# ursus-flow.net
KiCad netlist of a schematic drawn in EAGLE
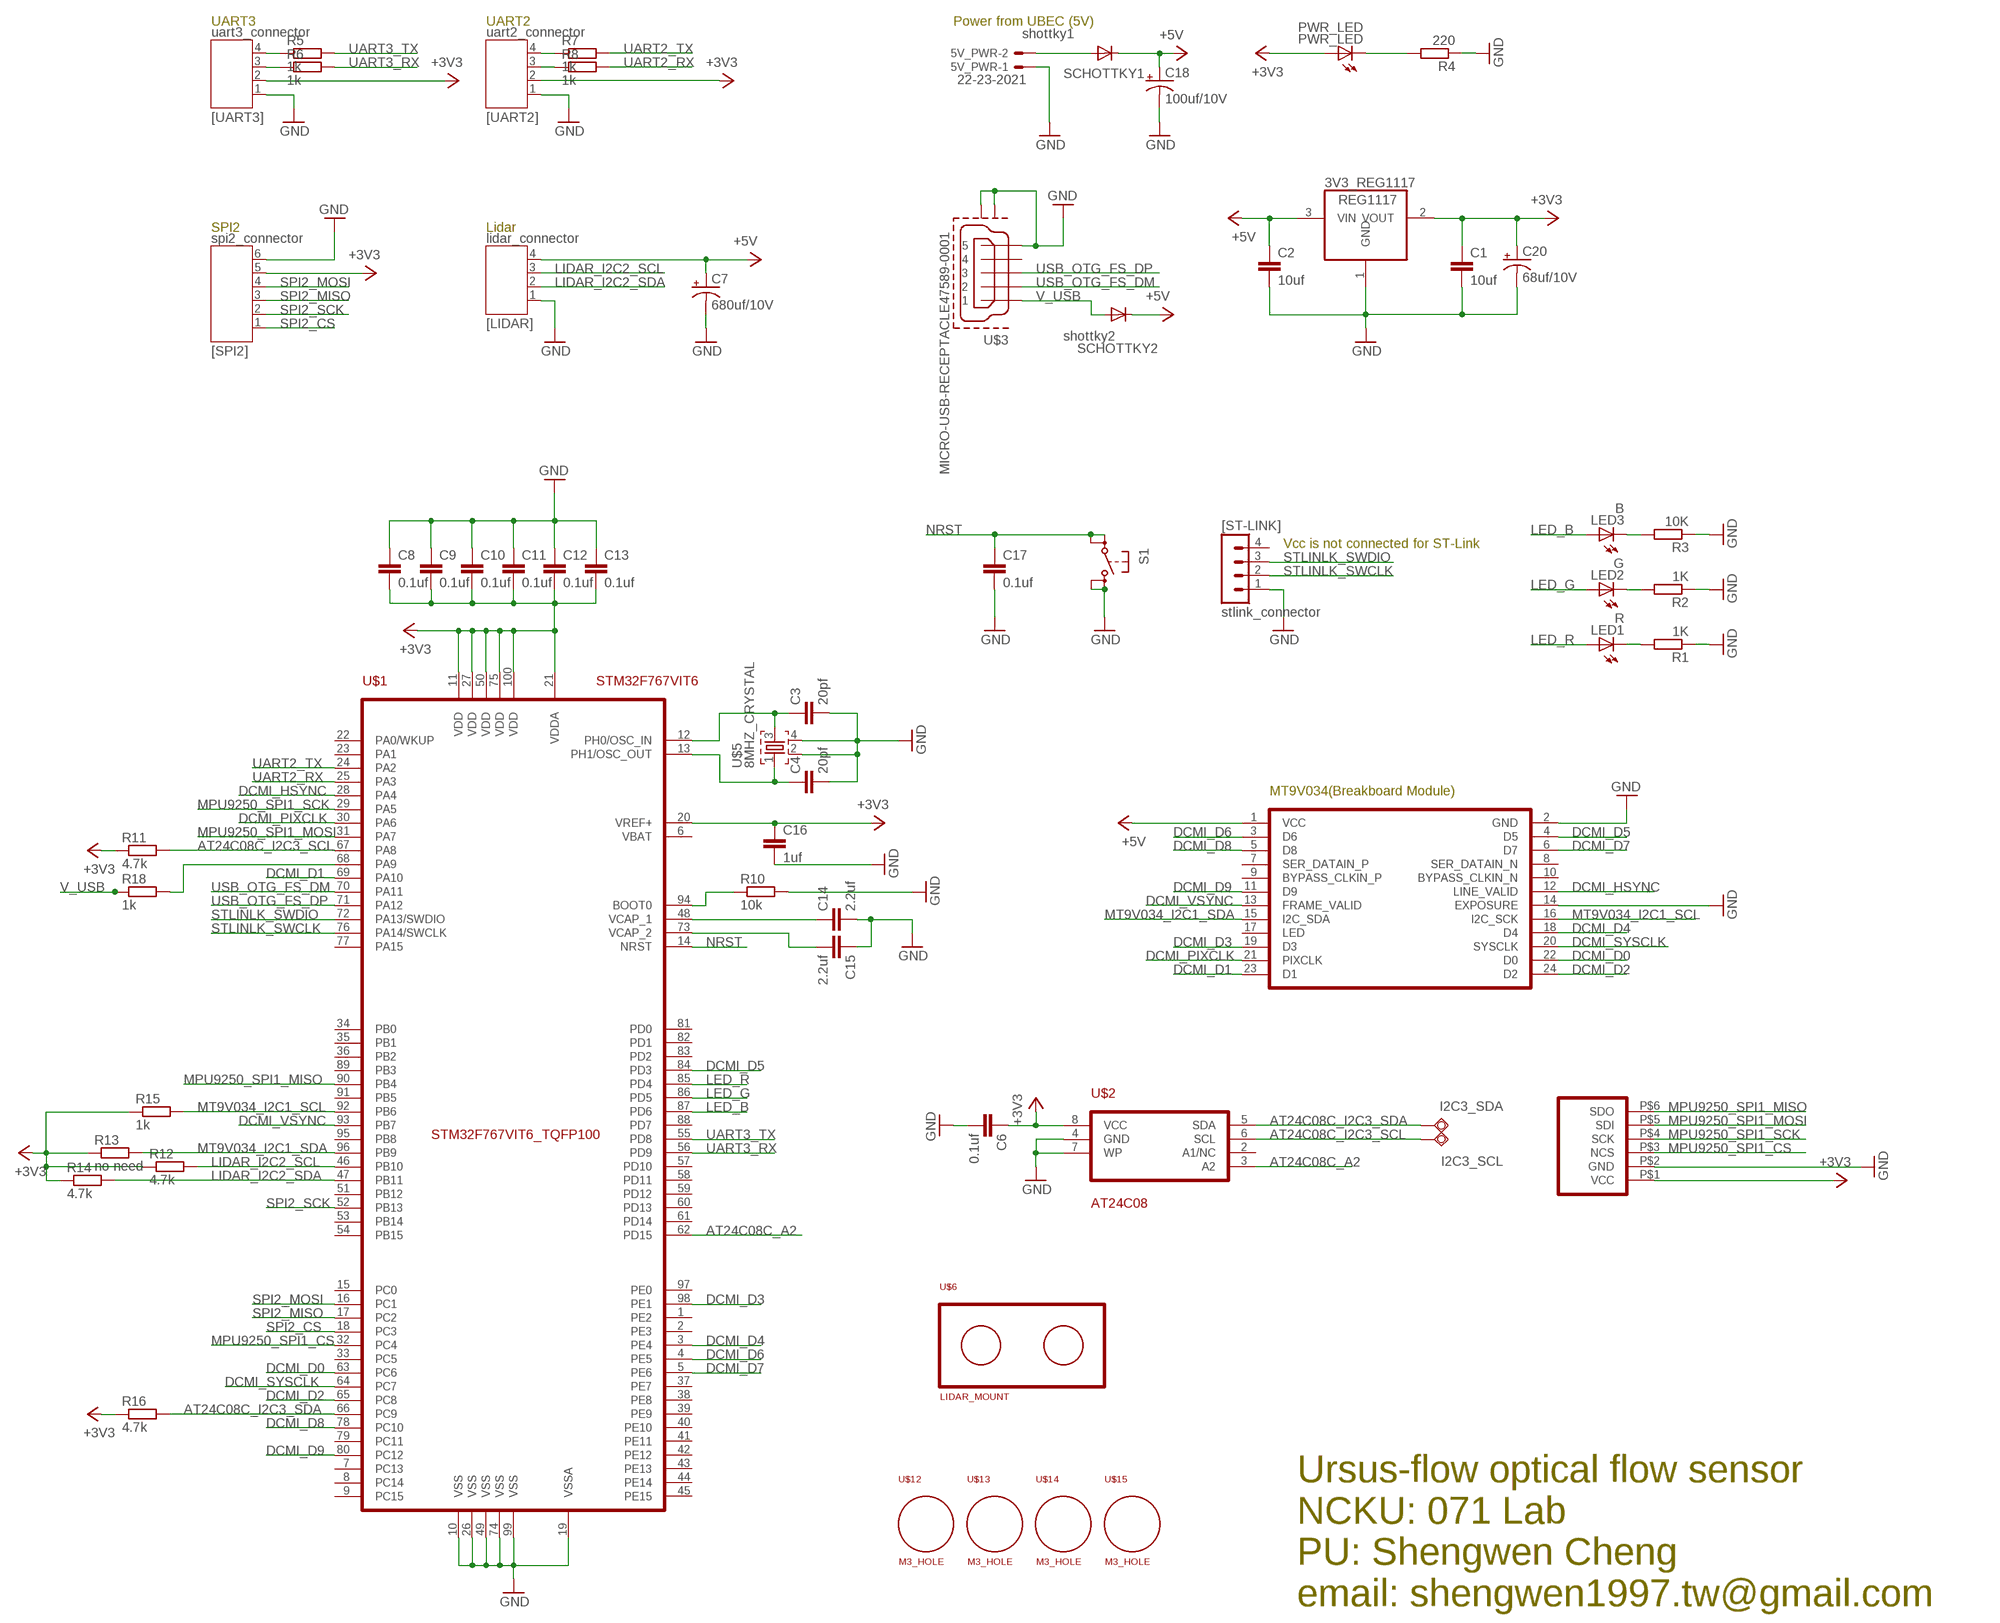
[diagram p0: schematic, sheet 1]

(export (version "E")
  (design (tool "Eeschema 10.0.6"))
  (components
    (comp (ref "3V3_REG1117")
      (value "REG1117")
      (footprint "eagle-import:SOT223")
      (libsource (lib "eagle-import") (part "REG1117"))
    )
    (comp (ref "5V_PWR")
      (value "22-23-2021")
      (footprint "eagle-import:22-23-2021")
      (fields (field (name "MF") "MOLEX"))
      (libsource (lib "eagle-import") (part "22-23-2021"))
    )
    (comp (ref "C1")
      (value "10uf")
      (footprint "eagle-import:C0805K")
      (libsource (lib "eagle-import") (part "C-EUC0805K"))
    )
    (comp (ref "C2")
      (value "10uf")
      (footprint "eagle-import:C0805K")
      (libsource (lib "eagle-import") (part "C-EUC0805K"))
    )
    (comp (ref "C3")
      (value "20pf")
      (footprint "eagle-import:C0805")
      (libsource (lib "eagle-import") (part "C-EUC0805"))
    )
    (comp (ref "C4")
      (value "20pf")
      (footprint "eagle-import:C0805")
      (libsource (lib "eagle-import") (part "C-EUC0805"))
    )
    (comp (ref "C6")
      (value "0.1uf")
      (footprint "eagle-import:C0805")
      (libsource (lib "eagle-import") (part "C-EUC0805"))
    )
    (comp (ref "C7")
      (value "680uf/10V")
      (footprint "eagle-import:D_7343-31W")
      (libsource (lib "eagle-import") (part "CPOL-USD/7343-31W"))
    )
    (comp (ref "C8")
      (value "0.1uf")
      (footprint "eagle-import:C0805")
      (libsource (lib "eagle-import") (part "C-EUC0805"))
    )
    (comp (ref "C9")
      (value "0.1uf")
      (footprint "eagle-import:C0805")
      (libsource (lib "eagle-import") (part "C-EUC0805"))
    )
    (comp (ref "C10")
      (value "0.1uf")
      (footprint "eagle-import:C0805")
      (libsource (lib "eagle-import") (part "C-EUC0805"))
    )
    (comp (ref "C11")
      (value "0.1uf")
      (footprint "eagle-import:C0805")
      (libsource (lib "eagle-import") (part "C-EUC0805"))
    )
    (comp (ref "C12")
      (value "0.1uf")
      (footprint "eagle-import:C0805")
      (libsource (lib "eagle-import") (part "C-EUC0805"))
    )
    (comp (ref "C13")
      (value "0.1uf")
      (footprint "eagle-import:C0805")
      (libsource (lib "eagle-import") (part "C-EUC0805"))
    )
    (comp (ref "C14")
      (value "2.2uf")
      (footprint "eagle-import:C0805")
      (libsource (lib "eagle-import") (part "C-EUC0805"))
    )
    (comp (ref "C15")
      (value "2.2uf")
      (footprint "eagle-import:C0805")
      (libsource (lib "eagle-import") (part "C-EUC0805"))
    )
    (comp (ref "C16")
      (value "1uf")
      (footprint "eagle-import:C0805")
      (libsource (lib "eagle-import") (part "C-EUC0805"))
    )
    (comp (ref "C17")
      (value "0.1uf")
      (footprint "eagle-import:C0805")
      (libsource (lib "eagle-import") (part "C-EUC0805"))
    )
    (comp (ref "C18")
      (value "100uf/10V")
      (footprint "eagle-import:C_6032-28R")
      (libsource (lib "eagle-import") (part "CPOL-USC/6032-28R"))
    )
    (comp (ref "C20")
      (value "68uf/10V")
      (footprint "eagle-import:B_3528-21W")
      (libsource (lib "eagle-import") (part "CPOL-USB/3528-21W"))
    )
    (comp (ref "I2C3_SCL")
      (value "TPSQTP20SQ")
      (footprint "eagle-import:TP20SQ")
      (libsource (lib "eagle-import") (part "TPSQTP20SQ"))
    )
    (comp (ref "I2C3_SDA")
      (value "TPSQTP20SQ")
      (footprint "eagle-import:TP20SQ")
      (libsource (lib "eagle-import") (part "TPSQTP20SQ"))
    )
    (comp (ref "LED1")
      (value "R")
      (footprint "eagle-import:SML0805")
      (libsource (lib "eagle-import") (part "LEDSML0805"))
    )
    (comp (ref "LED2")
      (value "G")
      (footprint "eagle-import:SML0805")
      (libsource (lib "eagle-import") (part "LEDSML0805"))
    )
    (comp (ref "LED3")
      (value "B")
      (footprint "eagle-import:SML0805")
      (libsource (lib "eagle-import") (part "LEDSML0805"))
    )
    (comp (ref "PWR_LED")
      (value "PWR_LED")
      (footprint "eagle-import:SML0805")
      (libsource (lib "eagle-import") (part "LEDSML0805"))
    )
    (comp (ref "R1")
      (value "1K")
      (footprint "eagle-import:R0805W")
      (libsource (lib "eagle-import") (part "resistor_R-EU_R0805W"))
    )
    (comp (ref "R2")
      (value "1K")
      (footprint "eagle-import:R0805W")
      (libsource (lib "eagle-import") (part "resistor_R-EU_R0805W"))
    )
    (comp (ref "R3")
      (value "10K")
      (footprint "eagle-import:R0805W")
      (libsource (lib "eagle-import") (part "resistor_R-EU_R0805W"))
    )
    (comp (ref "R4")
      (value "220")
      (footprint "eagle-import:R0805W")
      (libsource (lib "eagle-import") (part "resistor_R-EU_R0805W"))
    )
    (comp (ref "R5")
      (value "1k")
      (footprint "eagle-import:M0805")
      (libsource (lib "eagle-import") (part "R-EU_M0805"))
    )
    (comp (ref "R6")
      (value "1k")
      (footprint "eagle-import:M0805")
      (libsource (lib "eagle-import") (part "R-EU_M0805"))
    )
    (comp (ref "R7")
      (value "1k")
      (footprint "eagle-import:M0805")
      (libsource (lib "eagle-import") (part "R-EU_M0805"))
    )
    (comp (ref "R8")
      (value "1k")
      (footprint "eagle-import:M0805")
      (libsource (lib "eagle-import") (part "R-EU_M0805"))
    )
    (comp (ref "R10")
      (value "10k")
      (footprint "eagle-import:R0805W")
      (libsource (lib "eagle-import") (part "resistor_R-EU_R0805W"))
    )
    (comp (ref "R11")
      (value "4.7k")
      (footprint "eagle-import:R0805W")
      (libsource (lib "eagle-import") (part "resistor_R-EU_R0805W"))
    )
    (comp (ref "R12")
      (value "4.7k")
      (footprint "eagle-import:R0805W")
      (libsource (lib "eagle-import") (part "resistor_R-EU_R0805W"))
    )
    (comp (ref "R13")
      (value "no need")
      (footprint "eagle-import:R0805W")
      (libsource (lib "eagle-import") (part "resistor_R-EU_R0805W"))
    )
    (comp (ref "R14")
      (value "4.7k")
      (footprint "eagle-import:R0805W")
      (libsource (lib "eagle-import") (part "resistor_R-EU_R0805W"))
    )
    (comp (ref "R15")
      (value "1k")
      (footprint "eagle-import:R0805W")
      (libsource (lib "eagle-import") (part "resistor_R-EU_R0805W"))
    )
    (comp (ref "R16")
      (value "4.7k")
      (footprint "eagle-import:R0805W")
      (libsource (lib "eagle-import") (part "resistor_R-EU_R0805W"))
    )
    (comp (ref "R18")
      (value "1k")
      (footprint "eagle-import:R0805W")
      (libsource (lib "eagle-import") (part "resistor_R-EU_R0805W"))
    )
    (comp (ref "S1")
      (value "EVQPSL/Q")
      (footprint "eagle-import:EVQPSL_Q")
      (libsource (lib "eagle-import") (part "EVQPSL/Q"))
    )
    (comp (ref "SCHOTTKY1")
      (value "shottky1")
      (footprint "eagle-import:SOD323-W")
      (libsource (lib "eagle-import") (part "DIODE-SOD323-W"))
    )
    (comp (ref "SCHOTTKY2")
      (value "shottky2")
      (footprint "eagle-import:SOD323-W")
      (libsource (lib "eagle-import") (part "DIODE-SOD323-W"))
    )
    (comp (ref "U$1")
      (value "STM32F767VIT6")
      (footprint "eagle-import:STM32F767VIT6")
      (libsource (lib "eagle-import") (part "STM32F767VIT6"))
    )
    (comp (ref "U$2")
      (value "AT24C08")
      (footprint "eagle-import:SO8")
      (libsource (lib "eagle-import") (part "AT24C08"))
    )
    (comp (ref "U$3")
      (value "MICRO-USB-RECEPTACLE47589-0001")
      (footprint "eagle-import:47589-0001")
      (libsource (lib "eagle-import") (part "MICRO-USB-RECEPTACLE47589-0001"))
    )
    (comp (ref "U$4")
      (value "MT9V034_MODULE")
      (footprint "eagle-import:MA12-2")
      (libsource (lib "eagle-import") (part "MT9V034_MODULE"))
    )
    (comp (ref "U$5")
      (value "8MHZ_CRYSTAL")
      (footprint "eagle-import:8MHZ_CRYSTAL")
      (libsource (lib "eagle-import") (part "8MHZ_CRYSTAL"))
    )
    (comp (ref "U$6")
      (value "LIDAR_MOUNT")
      (footprint "eagle-import:LIDAR_MOUNT")
      (libsource (lib "eagle-import") (part "LIDAR_MOUNT"))
    )
    (comp (ref "U$11")
      (value "MPU9250_BREAKOUT")
      (footprint "eagle-import:MPU9250_BREAKOUT")
      (libsource (lib "eagle-import") (part "MPU9250_BREAKOUT"))
    )
    (comp (ref "U$12")
      (value "M3_HOLE")
      (footprint "eagle-import:M3_HOLE")
      (libsource (lib "eagle-import") (part "M3_HOLE"))
    )
    (comp (ref "U$13")
      (value "M3_HOLE")
      (footprint "eagle-import:M3_HOLE")
      (libsource (lib "eagle-import") (part "M3_HOLE"))
    )
    (comp (ref "U$14")
      (value "M3_HOLE")
      (footprint "eagle-import:M3_HOLE")
      (libsource (lib "eagle-import") (part "M3_HOLE"))
    )
    (comp (ref "U$15")
      (value "M3_HOLE")
      (footprint "eagle-import:M3_HOLE")
      (libsource (lib "eagle-import") (part "M3_HOLE"))
    )
    (comp (ref "[LIDAR]")
      (value "lidar_connector")
      (footprint "eagle-import:JST-PH4")
      (libsource (lib "eagle-import") (part "JST-PH4"))
    )
    (comp (ref "[SPI2]")
      (value "spi2_connector")
      (footprint "eagle-import:JST-PH6")
      (libsource (lib "eagle-import") (part "JST-PH6"))
    )
    (comp (ref "[ST-LINK]")
      (value "stlink_connector")
      (footprint "eagle-import:MA04-1")
      (libsource (lib "eagle-import") (part "MA04-1"))
    )
    (comp (ref "[UART2]")
      (value "uart2_connector")
      (footprint "eagle-import:JST-PH4")
      (libsource (lib "eagle-import") (part "JST-PH4"))
    )
    (comp (ref "[UART3]")
      (value "uart3_connector")
      (footprint "eagle-import:JST-PH4")
      (libsource (lib "eagle-import") (part "JST-PH4"))
    )
  )
  (nets
    (net (code "1") (name "+3V3") (class "Default")
      (node (ref "3V3_REG1117") (pin "2") (pinfunction "VOUT_2") (pintype "output"))
      (node (ref "C1") (pin "1") (pinfunction "1_1") (pintype "passive"))
      (node (ref "C10") (pin "2") (pinfunction "2_2") (pintype "passive"))
      (node (ref "C11") (pin "2") (pinfunction "2_2") (pintype "passive"))
      (node (ref "C12") (pin "2") (pinfunction "2_2") (pintype "passive"))
      (node (ref "C13") (pin "2") (pinfunction "2_2") (pintype "passive"))
      (node (ref "C16") (pin "1") (pinfunction "1_1") (pintype "passive"))
      (node (ref "C20") (pin "+") (pinfunction "+_+") (pintype "passive"))
      (node (ref "C6") (pin "1") (pinfunction "1_1") (pintype "passive"))
      (node (ref "C8") (pin "2") (pinfunction "2_2") (pintype "passive"))
      (node (ref "C9") (pin "2") (pinfunction "2_2") (pintype "passive"))
      (node (ref "PWR_LED") (pin "A") (pinfunction "A_A") (pintype "passive"))
      (node (ref "R11") (pin "1") (pinfunction "1_1") (pintype "passive"))
      (node (ref "R12") (pin "1") (pinfunction "1_1") (pintype "passive"))
      (node (ref "R13") (pin "1") (pinfunction "1_1") (pintype "passive"))
      (node (ref "R14") (pin "1") (pinfunction "1_1") (pintype "passive"))
      (node (ref "R15") (pin "1") (pinfunction "1_1") (pintype "passive"))
      (node (ref "R16") (pin "1") (pinfunction "1_1") (pintype "passive"))
      (node (ref "U$1") (pin "100") (pinfunction "VDD_100") (pintype "bidirectional"))
      (node (ref "U$1") (pin "11") (pinfunction "VDD_11") (pintype "bidirectional"))
      (node (ref "U$1") (pin "20") (pinfunction "VREF+_20") (pintype "bidirectional"))
      (node (ref "U$1") (pin "21") (pinfunction "VDDA_21") (pintype "bidirectional"))
      (node (ref "U$1") (pin "27") (pinfunction "VDD_27") (pintype "bidirectional"))
      (node (ref "U$1") (pin "50") (pinfunction "VDD_50") (pintype "bidirectional"))
      (node (ref "U$1") (pin "75") (pinfunction "VDD_75") (pintype "bidirectional"))
      (node (ref "U$11") (pin "P$1") (pinfunction "VCC_P$1") (pintype "bidirectional"))
      (node (ref "U$2") (pin "8") (pinfunction "VCC_8") (pintype "bidirectional"))
      (node (ref "[SPI2]") (pin "5") (pinfunction "5_5") (pintype "passive"))
      (node (ref "[UART2]") (pin "2") (pinfunction "2_2") (pintype "passive"))
      (node (ref "[UART3]") (pin "2") (pinfunction "2_2") (pintype "passive"))
    )
    (net (code "2") (name "+5V") (class "Default")
      (node (ref "3V3_REG1117") (pin "3") (pinfunction "VIN_3") (pintype "input"))
      (node (ref "C18") (pin "+") (pinfunction "+_+") (pintype "passive"))
      (node (ref "C2") (pin "1") (pinfunction "1_1") (pintype "passive"))
      (node (ref "C7") (pin "+") (pinfunction "+_+") (pintype "passive"))
      (node (ref "SCHOTTKY1") (pin "C") (pinfunction "C_C") (pintype "passive"))
      (node (ref "SCHOTTKY2") (pin "C") (pinfunction "C_C") (pintype "passive"))
      (node (ref "U$4") (pin "1") (pinfunction "VCC_1") (pintype "bidirectional"))
      (node (ref "[LIDAR]") (pin "4") (pinfunction "4_4") (pintype "passive"))
    )
    (net (code "3") (name "/AT24C08C_A2") (class "Default")
      (node (ref "U$1") (pin "62") (pinfunction "PD15_62") (pintype "bidirectional"))
      (node (ref "U$2") (pin "3") (pinfunction "A2_3") (pintype "bidirectional"))
    )
    (net (code "4") (name "/AT24C08C_I2C3_SCL") (class "Default")
      (node (ref "I2C3_SCL") (pin "TP") (pinfunction "TP_TP") (pintype "input"))
      (node (ref "R11") (pin "2") (pinfunction "2_2") (pintype "passive"))
      (node (ref "U$1") (pin "67") (pinfunction "PA8_67") (pintype "bidirectional"))
      (node (ref "U$2") (pin "6") (pinfunction "SCL_6") (pintype "bidirectional"))
    )
    (net (code "5") (name "/AT24C08C_I2C3_SDA") (class "Default")
      (node (ref "I2C3_SDA") (pin "TP") (pinfunction "TP_TP") (pintype "input"))
      (node (ref "R16") (pin "2") (pinfunction "2_2") (pintype "passive"))
      (node (ref "U$1") (pin "66") (pinfunction "PC9_66") (pintype "bidirectional"))
      (node (ref "U$2") (pin "5") (pinfunction "SDA_5") (pintype "bidirectional"))
    )
    (net (code "6") (name "/DCMI_D0") (class "Default")
      (node (ref "U$1") (pin "63") (pinfunction "PC6_63") (pintype "bidirectional"))
      (node (ref "U$4") (pin "22") (pinfunction "D0_22") (pintype "bidirectional"))
    )
    (net (code "7") (name "/DCMI_D1") (class "Default")
      (node (ref "U$1") (pin "69") (pinfunction "PA10_69") (pintype "bidirectional"))
      (node (ref "U$4") (pin "23") (pinfunction "D1_23") (pintype "bidirectional"))
    )
    (net (code "8") (name "/DCMI_D2") (class "Default")
      (node (ref "U$1") (pin "65") (pinfunction "PC8_65") (pintype "bidirectional"))
      (node (ref "U$4") (pin "24") (pinfunction "D2_24") (pintype "bidirectional"))
    )
    (net (code "9") (name "/DCMI_D3") (class "Default")
      (node (ref "U$1") (pin "98") (pinfunction "PE1_98") (pintype "bidirectional"))
      (node (ref "U$4") (pin "19") (pinfunction "D3_19") (pintype "bidirectional"))
    )
    (net (code "10") (name "/DCMI_D4") (class "Default")
      (node (ref "U$1") (pin "3") (pinfunction "PE4_3") (pintype "bidirectional"))
      (node (ref "U$4") (pin "18") (pinfunction "D4_18") (pintype "bidirectional"))
    )
    (net (code "11") (name "/DCMI_D5") (class "Default")
      (node (ref "U$1") (pin "84") (pinfunction "PD3_84") (pintype "bidirectional"))
      (node (ref "U$4") (pin "4") (pinfunction "D5_4") (pintype "bidirectional"))
    )
    (net (code "12") (name "/DCMI_D6") (class "Default")
      (node (ref "U$1") (pin "4") (pinfunction "PE5_4") (pintype "bidirectional"))
      (node (ref "U$4") (pin "3") (pinfunction "D6_3") (pintype "bidirectional"))
    )
    (net (code "13") (name "/DCMI_D7") (class "Default")
      (node (ref "U$1") (pin "5") (pinfunction "PE6_5") (pintype "bidirectional"))
      (node (ref "U$4") (pin "6") (pinfunction "D7_6") (pintype "bidirectional"))
    )
    (net (code "14") (name "/DCMI_D8") (class "Default")
      (node (ref "U$1") (pin "78") (pinfunction "PC10_78") (pintype "bidirectional"))
      (node (ref "U$4") (pin "5") (pinfunction "D8_5") (pintype "bidirectional"))
    )
    (net (code "15") (name "/DCMI_D9") (class "Default")
      (node (ref "U$1") (pin "80") (pinfunction "PC12_80") (pintype "bidirectional"))
      (node (ref "U$4") (pin "11") (pinfunction "D9_11") (pintype "bidirectional"))
    )
    (net (code "16") (name "/DCMI_HSYNC") (class "Default")
      (node (ref "U$1") (pin "28") (pinfunction "PA4_28") (pintype "bidirectional"))
      (node (ref "U$4") (pin "12") (pinfunction "LINE_VALID_12") (pintype "bidirectional"))
    )
    (net (code "17") (name "/DCMI_PIXCLK") (class "Default")
      (node (ref "U$1") (pin "30") (pinfunction "PA6_30") (pintype "bidirectional"))
      (node (ref "U$4") (pin "21") (pinfunction "PIXCLK_21") (pintype "bidirectional"))
    )
    (net (code "18") (name "/DCMI_SYSCLK") (class "Default")
      (node (ref "U$1") (pin "64") (pinfunction "PC7_64") (pintype "bidirectional"))
      (node (ref "U$4") (pin "20") (pinfunction "SYSCLK_20") (pintype "bidirectional"))
    )
    (net (code "19") (name "/DCMI_VSYNC") (class "Default")
      (node (ref "U$1") (pin "93") (pinfunction "PB7_93") (pintype "bidirectional"))
      (node (ref "U$4") (pin "13") (pinfunction "FRAME_VALID_13") (pintype "bidirectional"))
    )
    (net (code "20") (name "/LED_B") (class "Default")
      (node (ref "LED3") (pin "A") (pinfunction "A_A") (pintype "passive"))
      (node (ref "U$1") (pin "87") (pinfunction "PD6_87") (pintype "bidirectional"))
    )
    (net (code "21") (name "/LED_G") (class "Default")
      (node (ref "LED2") (pin "A") (pinfunction "A_A") (pintype "passive"))
      (node (ref "U$1") (pin "86") (pinfunction "PD5_86") (pintype "bidirectional"))
    )
    (net (code "22") (name "/LED_R") (class "Default")
      (node (ref "LED1") (pin "A") (pinfunction "A_A") (pintype "passive"))
      (node (ref "U$1") (pin "85") (pinfunction "PD4_85") (pintype "bidirectional"))
    )
    (net (code "23") (name "/LIDAR_I2C2_SCL") (class "Default")
      (node (ref "R12") (pin "2") (pinfunction "2_2") (pintype "passive"))
      (node (ref "U$1") (pin "46") (pinfunction "PB10_46") (pintype "bidirectional"))
      (node (ref "[LIDAR]") (pin "3") (pinfunction "3_3") (pintype "passive"))
    )
    (net (code "24") (name "/LIDAR_I2C2_SDA") (class "Default")
      (node (ref "R14") (pin "2") (pinfunction "2_2") (pintype "passive"))
      (node (ref "U$1") (pin "47") (pinfunction "PB11_47") (pintype "bidirectional"))
      (node (ref "[LIDAR]") (pin "2") (pinfunction "2_2") (pintype "passive"))
    )
    (net (code "25") (name "/MPU9250_SPI1_CS") (class "Default")
      (node (ref "U$1") (pin "32") (pinfunction "PC4_32") (pintype "bidirectional"))
      (node (ref "U$11") (pin "P$3") (pinfunction "NCS_P$3") (pintype "bidirectional"))
    )
    (net (code "26") (name "/MPU9250_SPI1_MISO") (class "Default")
      (node (ref "U$1") (pin "90") (pinfunction "PB4_90") (pintype "bidirectional"))
      (node (ref "U$11") (pin "P$6") (pinfunction "SDO_P$6") (pintype "bidirectional"))
    )
    (net (code "27") (name "/MPU9250_SPI1_MOSI") (class "Default")
      (node (ref "U$1") (pin "31") (pinfunction "PA7_31") (pintype "bidirectional"))
      (node (ref "U$11") (pin "P$5") (pinfunction "SDI_P$5") (pintype "bidirectional"))
    )
    (net (code "28") (name "/MPU9250_SPI1_SCK") (class "Default")
      (node (ref "U$1") (pin "29") (pinfunction "PA5_29") (pintype "bidirectional"))
      (node (ref "U$11") (pin "P$4") (pinfunction "SCK_P$4") (pintype "bidirectional"))
    )
    (net (code "29") (name "/MT9V034_I2C1_SCL") (class "Default")
      (node (ref "R15") (pin "2") (pinfunction "2_2") (pintype "passive"))
      (node (ref "U$1") (pin "92") (pinfunction "PB6_92") (pintype "bidirectional"))
      (node (ref "U$4") (pin "16") (pinfunction "I2C_SCK_16") (pintype "bidirectional"))
    )
    (net (code "30") (name "/MT9V034_I2C1_SDA") (class "Default")
      (node (ref "R13") (pin "2") (pinfunction "2_2") (pintype "passive"))
      (node (ref "U$1") (pin "96") (pinfunction "PB9_96") (pintype "bidirectional"))
      (node (ref "U$4") (pin "15") (pinfunction "I2C_SDA_15") (pintype "bidirectional"))
    )
    (net (code "31") (name "/NRST") (class "Default")
      (node (ref "C17") (pin "1") (pinfunction "1_1") (pintype "passive"))
      (node (ref "S1") (pin "A") (pinfunction "P_A") (pintype "passive"))
      (node (ref "S1") (pin "A1") (pinfunction "P1_A1") (pintype "passive"))
      (node (ref "U$1") (pin "14") (pinfunction "NRST_14") (pintype "bidirectional"))
    )
    (net (code "32") (name "/SPI2_CS") (class "Default")
      (node (ref "U$1") (pin "18") (pinfunction "PC3_18") (pintype "bidirectional"))
      (node (ref "[SPI2]") (pin "1") (pinfunction "1_1") (pintype "passive"))
    )
    (net (code "33") (name "/SPI2_MISO") (class "Default")
      (node (ref "U$1") (pin "17") (pinfunction "PC2_17") (pintype "bidirectional"))
      (node (ref "[SPI2]") (pin "3") (pinfunction "3_3") (pintype "passive"))
    )
    (net (code "34") (name "/SPI2_MOSI") (class "Default")
      (node (ref "U$1") (pin "16") (pinfunction "PC1_16") (pintype "bidirectional"))
      (node (ref "[SPI2]") (pin "4") (pinfunction "4_4") (pintype "passive"))
    )
    (net (code "35") (name "/SPI2_SCK") (class "Default")
      (node (ref "U$1") (pin "52") (pinfunction "PB13_52") (pintype "bidirectional"))
      (node (ref "[SPI2]") (pin "2") (pinfunction "2_2") (pintype "passive"))
    )
    (net (code "36") (name "/STLINLK_SWCLK") (class "Default")
      (node (ref "U$1") (pin "76") (pinfunction "PA14/SWCLK_76") (pintype "bidirectional"))
      (node (ref "[ST-LINK]") (pin "2") (pinfunction "2_2") (pintype "passive"))
    )
    (net (code "37") (name "/STLINLK_SWDIO") (class "Default")
      (node (ref "U$1") (pin "72") (pinfunction "PA13/SWDIO_72") (pintype "bidirectional"))
      (node (ref "[ST-LINK]") (pin "3") (pinfunction "3_3") (pintype "passive"))
    )
    (net (code "38") (name "/UART2_RX") (class "Default")
      (node (ref "R8") (pin "2") (pinfunction "2_2") (pintype "passive"))
      (node (ref "U$1") (pin "25") (pinfunction "PA3_25") (pintype "bidirectional"))
    )
    (net (code "39") (name "/UART2_TX") (class "Default")
      (node (ref "R7") (pin "2") (pinfunction "2_2") (pintype "passive"))
      (node (ref "U$1") (pin "24") (pinfunction "PA2_24") (pintype "bidirectional"))
    )
    (net (code "40") (name "/UART3_RX") (class "Default")
      (node (ref "R6") (pin "2") (pinfunction "2_2") (pintype "passive"))
      (node (ref "U$1") (pin "56") (pinfunction "PD9_56") (pintype "bidirectional"))
    )
    (net (code "41") (name "/UART3_TX") (class "Default")
      (node (ref "R5") (pin "2") (pinfunction "2_2") (pintype "passive"))
      (node (ref "U$1") (pin "55") (pinfunction "PD8_55") (pintype "bidirectional"))
    )
    (net (code "42") (name "/USB_OTG_FS_DM") (class "Default")
      (node (ref "U$1") (pin "70") (pinfunction "PA11_70") (pintype "bidirectional"))
      (node (ref "U$3") (pin "2") (pinfunction "2_2") (pintype "input"))
    )
    (net (code "43") (name "/USB_OTG_FS_DP") (class "Default")
      (node (ref "U$1") (pin "71") (pinfunction "PA12_71") (pintype "bidirectional"))
      (node (ref "U$3") (pin "3") (pinfunction "3_3") (pintype "input"))
    )
    (net (code "44") (name "/V_USB") (class "Default")
      (node (ref "R18") (pin "1") (pinfunction "1_1") (pintype "passive"))
      (node (ref "SCHOTTKY2") (pin "A") (pinfunction "A_A") (pintype "passive"))
      (node (ref "U$3") (pin "1") (pinfunction "1_1") (pintype "input"))
    )
    (net (code "45") (name "GND") (class "Default")
      (node (ref "3V3_REG1117") (pin "1") (pinfunction "GND_1") (pintype "power_in"))
      (node (ref "5V_PWR") (pin "1") (pinfunction "S_1") (pintype "passive"))
      (node (ref "C1") (pin "2") (pinfunction "2_2") (pintype "passive"))
      (node (ref "C10") (pin "1") (pinfunction "1_1") (pintype "passive"))
      (node (ref "C11") (pin "1") (pinfunction "1_1") (pintype "passive"))
      (node (ref "C12") (pin "1") (pinfunction "1_1") (pintype "passive"))
      (node (ref "C13") (pin "1") (pinfunction "1_1") (pintype "passive"))
      (node (ref "C14") (pin "2") (pinfunction "2_2") (pintype "passive"))
      (node (ref "C15") (pin "1") (pinfunction "1_1") (pintype "passive"))
      (node (ref "C16") (pin "2") (pinfunction "2_2") (pintype "passive"))
      (node (ref "C17") (pin "2") (pinfunction "2_2") (pintype "passive"))
      (node (ref "C18") (pin "-") (pinfunction "-_-") (pintype "passive"))
      (node (ref "C2") (pin "2") (pinfunction "2_2") (pintype "passive"))
      (node (ref "C20") (pin "-") (pinfunction "-_-") (pintype "passive"))
      (node (ref "C3") (pin "2") (pinfunction "2_2") (pintype "passive"))
      (node (ref "C4") (pin "2") (pinfunction "2_2") (pintype "passive"))
      (node (ref "C6") (pin "2") (pinfunction "2_2") (pintype "passive"))
      (node (ref "C7") (pin "-") (pinfunction "-_-") (pintype "passive"))
      (node (ref "C8") (pin "1") (pinfunction "1_1") (pintype "passive"))
      (node (ref "C9") (pin "1") (pinfunction "1_1") (pintype "passive"))
      (node (ref "R1") (pin "1") (pinfunction "1_1") (pintype "passive"))
      (node (ref "R10") (pin "2") (pinfunction "2_2") (pintype "passive"))
      (node (ref "R2") (pin "1") (pinfunction "1_1") (pintype "passive"))
      (node (ref "R3") (pin "1") (pinfunction "1_1") (pintype "passive"))
      (node (ref "R4") (pin "1") (pinfunction "1_1") (pintype "passive"))
      (node (ref "S1") (pin "B") (pinfunction "S_B") (pintype "passive"))
      (node (ref "S1") (pin "B1") (pinfunction "S1_B1") (pintype "passive"))
      (node (ref "U$1") (pin "10") (pinfunction "VSS_10") (pintype "bidirectional"))
      (node (ref "U$1") (pin "19") (pinfunction "VSSA_19") (pintype "bidirectional"))
      (node (ref "U$1") (pin "26") (pinfunction "VSS_26") (pintype "bidirectional"))
      (node (ref "U$1") (pin "49") (pinfunction "VSS_49") (pintype "bidirectional"))
      (node (ref "U$1") (pin "74") (pinfunction "VSS_74") (pintype "bidirectional"))
      (node (ref "U$1") (pin "99") (pinfunction "VSS_99") (pintype "bidirectional"))
      (node (ref "U$11") (pin "P$2") (pinfunction "GND_P$2") (pintype "bidirectional"))
      (node (ref "U$2") (pin "4") (pinfunction "GND_4") (pintype "bidirectional"))
      (node (ref "U$2") (pin "7") (pinfunction "WP_7") (pintype "bidirectional"))
      (node (ref "U$3") (pin "5") (pinfunction "5_5") (pintype "input"))
      (node (ref "U$3") (pin "CASING1") (pinfunction "GND1_CASING1") (pintype "bidirectional"))
      (node (ref "U$3") (pin "CASING2") (pinfunction "GND2_CASING2") (pintype "bidirectional"))
      (node (ref "U$4") (pin "14") (pinfunction "EXPOSURE_14") (pintype "bidirectional"))
      (node (ref "U$4") (pin "2") (pinfunction "GND_2") (pintype "bidirectional"))
      (node (ref "U$5") (pin "2") (pinfunction "2_2") (pintype "passive"))
      (node (ref "U$5") (pin "4") (pinfunction "4_4") (pintype "passive"))
      (node (ref "[LIDAR]") (pin "1") (pinfunction "1_1") (pintype "passive"))
      (node (ref "[SPI2]") (pin "6") (pinfunction "6_6") (pintype "passive"))
      (node (ref "[ST-LINK]") (pin "1") (pinfunction "1_1") (pintype "passive"))
      (node (ref "[UART2]") (pin "1") (pinfunction "1_1") (pintype "passive"))
      (node (ref "[UART3]") (pin "1") (pinfunction "1_1") (pintype "passive"))
    )
    (net (code "46") (name "Net-(5V_PWRB-S)") (class "Default")
      (node (ref "5V_PWR") (pin "2") (pinfunction "S_2") (pintype "passive"))
      (node (ref "SCHOTTKY1") (pin "A") (pinfunction "A_A") (pintype "passive"))
    )
    (net (code "47") (name "Net-(LED1-PadC)") (class "Default")
      (node (ref "LED1") (pin "C") (pinfunction "C_C") (pintype "passive"))
      (node (ref "R1") (pin "2") (pinfunction "2_2") (pintype "passive"))
    )
    (net (code "48") (name "Net-(LED2-PadC)") (class "Default")
      (node (ref "LED2") (pin "C") (pinfunction "C_C") (pintype "passive"))
      (node (ref "R2") (pin "2") (pinfunction "2_2") (pintype "passive"))
    )
    (net (code "49") (name "Net-(LED3-PadC)") (class "Default")
      (node (ref "LED3") (pin "C") (pinfunction "C_C") (pintype "passive"))
      (node (ref "R3") (pin "2") (pinfunction "2_2") (pintype "passive"))
    )
    (net (code "50") (name "Net-(PWR_LED-PadC)") (class "Default")
      (node (ref "PWR_LED") (pin "C") (pinfunction "C_C") (pintype "passive"))
      (node (ref "R4") (pin "2") (pinfunction "2_2") (pintype "passive"))
    )
    (net (code "51") (name "Net-(R5-Pad1)") (class "Default")
      (node (ref "R5") (pin "1") (pinfunction "1_1") (pintype "passive"))
      (node (ref "[UART3]") (pin "4") (pinfunction "4_4") (pintype "passive"))
    )
    (net (code "52") (name "Net-(R6-Pad1)") (class "Default")
      (node (ref "R6") (pin "1") (pinfunction "1_1") (pintype "passive"))
      (node (ref "[UART3]") (pin "3") (pinfunction "3_3") (pintype "passive"))
    )
    (net (code "53") (name "Net-(R7-Pad1)") (class "Default")
      (node (ref "R7") (pin "1") (pinfunction "1_1") (pintype "passive"))
      (node (ref "[UART2]") (pin "4") (pinfunction "4_4") (pintype "passive"))
    )
    (net (code "54") (name "Net-(R8-Pad1)") (class "Default")
      (node (ref "R8") (pin "1") (pinfunction "1_1") (pintype "passive"))
      (node (ref "[UART2]") (pin "3") (pinfunction "3_3") (pintype "passive"))
    )
    (net (code "55") (name "Net-(U$1-BOOT0)") (class "Default")
      (node (ref "R10") (pin "1") (pinfunction "1_1") (pintype "passive"))
      (node (ref "U$1") (pin "94") (pinfunction "BOOT0_94") (pintype "bidirectional"))
    )
    (net (code "56") (name "Net-(U$1-PA9)") (class "Default")
      (node (ref "R18") (pin "2") (pinfunction "2_2") (pintype "passive"))
      (node (ref "U$1") (pin "68") (pinfunction "PA9_68") (pintype "bidirectional"))
    )
    (net (code "57") (name "Net-(U$1-PH0{slash}OSC_IN)") (class "Default")
      (node (ref "C3") (pin "1") (pinfunction "1_1") (pintype "passive"))
      (node (ref "U$1") (pin "12") (pinfunction "PH0/OSC_IN_12") (pintype "bidirectional"))
      (node (ref "U$5") (pin "3") (pinfunction "3_3") (pintype "passive"))
    )
    (net (code "58") (name "Net-(U$1-PH1{slash}OSC_OUT)") (class "Default")
      (node (ref "C4") (pin "1") (pinfunction "1_1") (pintype "passive"))
      (node (ref "U$1") (pin "13") (pinfunction "PH1/OSC_OUT_13") (pintype "bidirectional"))
      (node (ref "U$5") (pin "1") (pinfunction "1_1") (pintype "passive"))
    )
    (net (code "59") (name "Net-(U$1-VCAP_1)") (class "Default")
      (node (ref "C14") (pin "1") (pinfunction "1_1") (pintype "passive"))
      (node (ref "U$1") (pin "48") (pinfunction "VCAP_1_48") (pintype "bidirectional"))
    )
    (net (code "60") (name "Net-(U$1-VCAP_2)") (class "Default")
      (node (ref "C15") (pin "2") (pinfunction "2_2") (pintype "passive"))
      (node (ref "U$1") (pin "73") (pinfunction "VCAP_2_73") (pintype "bidirectional"))
    )
    (net (code "61") (name "unconnected-(U$1-PA0{slash}WKUP-Pad22)") (class "Default")
      (node (ref "U$1") (pin "22") (pinfunction "PA0/WKUP_22") (pintype "bidirectional"))
    )
    (net (code "62") (name "unconnected-(U$1-PA1-Pad23)") (class "Default")
      (node (ref "U$1") (pin "23") (pinfunction "PA1_23") (pintype "bidirectional"))
    )
    (net (code "63") (name "unconnected-(U$1-PA15-Pad77)") (class "Default")
      (node (ref "U$1") (pin "77") (pinfunction "PA15_77") (pintype "bidirectional"))
    )
    (net (code "64") (name "unconnected-(U$1-PB0-Pad34)") (class "Default")
      (node (ref "U$1") (pin "34") (pinfunction "PB0_34") (pintype "bidirectional"))
    )
    (net (code "65") (name "unconnected-(U$1-PB1-Pad35)") (class "Default")
      (node (ref "U$1") (pin "35") (pinfunction "PB1_35") (pintype "bidirectional"))
    )
    (net (code "66") (name "unconnected-(U$1-PB2-Pad36)") (class "Default")
      (node (ref "U$1") (pin "36") (pinfunction "PB2_36") (pintype "bidirectional"))
    )
    (net (code "67") (name "unconnected-(U$1-PB3-Pad89)") (class "Default")
      (node (ref "U$1") (pin "89") (pinfunction "PB3_89") (pintype "bidirectional"))
    )
    (net (code "68") (name "unconnected-(U$1-PB5-Pad91)") (class "Default")
      (node (ref "U$1") (pin "91") (pinfunction "PB5_91") (pintype "bidirectional"))
    )
    (net (code "69") (name "unconnected-(U$1-PB8-Pad95)") (class "Default")
      (node (ref "U$1") (pin "95") (pinfunction "PB8_95") (pintype "bidirectional"))
    )
    (net (code "70") (name "unconnected-(U$1-PB12-Pad51)") (class "Default")
      (node (ref "U$1") (pin "51") (pinfunction "PB12_51") (pintype "bidirectional"))
    )
    (net (code "71") (name "unconnected-(U$1-PB14-Pad53)") (class "Default")
      (node (ref "U$1") (pin "53") (pinfunction "PB14_53") (pintype "bidirectional"))
    )
    (net (code "72") (name "unconnected-(U$1-PB15-Pad54)") (class "Default")
      (node (ref "U$1") (pin "54") (pinfunction "PB15_54") (pintype "bidirectional"))
    )
    (net (code "73") (name "unconnected-(U$1-PC0-Pad15)") (class "Default")
      (node (ref "U$1") (pin "15") (pinfunction "PC0_15") (pintype "bidirectional"))
    )
    (net (code "74") (name "unconnected-(U$1-PC5-Pad33)") (class "Default")
      (node (ref "U$1") (pin "33") (pinfunction "PC5_33") (pintype "bidirectional"))
    )
    (net (code "75") (name "unconnected-(U$1-PC11-Pad79)") (class "Default")
      (node (ref "U$1") (pin "79") (pinfunction "PC11_79") (pintype "bidirectional"))
    )
    (net (code "76") (name "unconnected-(U$1-PC13-Pad7)") (class "Default")
      (node (ref "U$1") (pin "7") (pinfunction "PC13_7") (pintype "bidirectional"))
    )
    (net (code "77") (name "unconnected-(U$1-PC14-Pad8)") (class "Default")
      (node (ref "U$1") (pin "8") (pinfunction "PC14_8") (pintype "bidirectional"))
    )
    (net (code "78") (name "unconnected-(U$1-PC15-Pad9)") (class "Default")
      (node (ref "U$1") (pin "9") (pinfunction "PC15_9") (pintype "bidirectional"))
    )
    (net (code "79") (name "unconnected-(U$1-PD0-Pad81)") (class "Default")
      (node (ref "U$1") (pin "81") (pinfunction "PD0_81") (pintype "bidirectional"))
    )
    (net (code "80") (name "unconnected-(U$1-PD1-Pad82)") (class "Default")
      (node (ref "U$1") (pin "82") (pinfunction "PD1_82") (pintype "bidirectional"))
    )
    (net (code "81") (name "unconnected-(U$1-PD2-Pad83)") (class "Default")
      (node (ref "U$1") (pin "83") (pinfunction "PD2_83") (pintype "bidirectional"))
    )
    (net (code "82") (name "unconnected-(U$1-PD7-Pad88)") (class "Default")
      (node (ref "U$1") (pin "88") (pinfunction "PD7_88") (pintype "bidirectional"))
    )
    (net (code "83") (name "unconnected-(U$1-PD10-Pad57)") (class "Default")
      (node (ref "U$1") (pin "57") (pinfunction "PD10_57") (pintype "bidirectional"))
    )
    (net (code "84") (name "unconnected-(U$1-PD11-Pad58)") (class "Default")
      (node (ref "U$1") (pin "58") (pinfunction "PD11_58") (pintype "bidirectional"))
    )
    (net (code "85") (name "unconnected-(U$1-PD12-Pad59)") (class "Default")
      (node (ref "U$1") (pin "59") (pinfunction "PD12_59") (pintype "bidirectional"))
    )
    (net (code "86") (name "unconnected-(U$1-PD13-Pad60)") (class "Default")
      (node (ref "U$1") (pin "60") (pinfunction "PD13_60") (pintype "bidirectional"))
    )
    (net (code "87") (name "unconnected-(U$1-PD14-Pad61)") (class "Default")
      (node (ref "U$1") (pin "61") (pinfunction "PD14_61") (pintype "bidirectional"))
    )
    (net (code "88") (name "unconnected-(U$1-PE0-Pad97)") (class "Default")
      (node (ref "U$1") (pin "97") (pinfunction "PE0_97") (pintype "bidirectional"))
    )
    (net (code "89") (name "unconnected-(U$1-PE2-Pad1)") (class "Default")
      (node (ref "U$1") (pin "1") (pinfunction "PE2_1") (pintype "bidirectional"))
    )
    (net (code "90") (name "unconnected-(U$1-PE3-Pad2)") (class "Default")
      (node (ref "U$1") (pin "2") (pinfunction "PE3_2") (pintype "bidirectional"))
    )
    (net (code "91") (name "unconnected-(U$1-PE7-Pad37)") (class "Default")
      (node (ref "U$1") (pin "37") (pinfunction "PE7_37") (pintype "bidirectional"))
    )
    (net (code "92") (name "unconnected-(U$1-PE8-Pad38)") (class "Default")
      (node (ref "U$1") (pin "38") (pinfunction "PE8_38") (pintype "bidirectional"))
    )
    (net (code "93") (name "unconnected-(U$1-PE9-Pad39)") (class "Default")
      (node (ref "U$1") (pin "39") (pinfunction "PE9_39") (pintype "bidirectional"))
    )
    (net (code "94") (name "unconnected-(U$1-PE10-Pad40)") (class "Default")
      (node (ref "U$1") (pin "40") (pinfunction "PE10_40") (pintype "bidirectional"))
    )
    (net (code "95") (name "unconnected-(U$1-PE11-Pad41)") (class "Default")
      (node (ref "U$1") (pin "41") (pinfunction "PE11_41") (pintype "bidirectional"))
    )
    (net (code "96") (name "unconnected-(U$1-PE12-Pad42)") (class "Default")
      (node (ref "U$1") (pin "42") (pinfunction "PE12_42") (pintype "bidirectional"))
    )
    (net (code "97") (name "unconnected-(U$1-PE13-Pad43)") (class "Default")
      (node (ref "U$1") (pin "43") (pinfunction "PE13_43") (pintype "bidirectional"))
    )
    (net (code "98") (name "unconnected-(U$1-PE14-Pad44)") (class "Default")
      (node (ref "U$1") (pin "44") (pinfunction "PE14_44") (pintype "bidirectional"))
    )
    (net (code "99") (name "unconnected-(U$1-PE15-Pad45)") (class "Default")
      (node (ref "U$1") (pin "45") (pinfunction "PE15_45") (pintype "bidirectional"))
    )
    (net (code "100") (name "unconnected-(U$1-VBAT-Pad6)") (class "Default")
      (node (ref "U$1") (pin "6") (pinfunction "VBAT_6") (pintype "bidirectional"))
    )
    (net (code "101") (name "unconnected-(U$2-A1{slash}NC-Pad2)") (class "Default")
      (node (ref "U$2") (pin "2") (pinfunction "A1/NC_2") (pintype "bidirectional"))
    )
    (net (code "102") (name "unconnected-(U$3-Pad4)") (class "Default")
      (node (ref "U$3") (pin "4") (pinfunction "4_4") (pintype "input"))
    )
    (net (code "103") (name "unconnected-(U$4-BYPASS_CLKIN_N-Pad10)") (class "Default")
      (node (ref "U$4") (pin "10") (pinfunction "BYPASS_CLKIN_N_10") (pintype "bidirectional"))
    )
    (net (code "104") (name "unconnected-(U$4-BYPASS_CLKIN_P-Pad9)") (class "Default")
      (node (ref "U$4") (pin "9") (pinfunction "BYPASS_CLKIN_P_9") (pintype "bidirectional"))
    )
    (net (code "105") (name "unconnected-(U$4-LED-Pad17)") (class "Default")
      (node (ref "U$4") (pin "17") (pinfunction "LED_17") (pintype "bidirectional"))
    )
    (net (code "106") (name "unconnected-(U$4-SER_DATAIN_N-Pad8)") (class "Default")
      (node (ref "U$4") (pin "8") (pinfunction "SER_DATAIN_N_8") (pintype "bidirectional"))
    )
    (net (code "107") (name "unconnected-(U$4-SER_DATAIN_P-Pad7)") (class "Default")
      (node (ref "U$4") (pin "7") (pinfunction "SER_DATAIN_P_7") (pintype "bidirectional"))
    )
    (net (code "108") (name "unconnected-([ST-LINK]-Pad4)") (class "Default")
      (node (ref "[ST-LINK]") (pin "4") (pinfunction "4_4") (pintype "passive"))
    )
  )
)
